# dskrdy.net
KiCad netlist of a schematic drawn in EAGLE
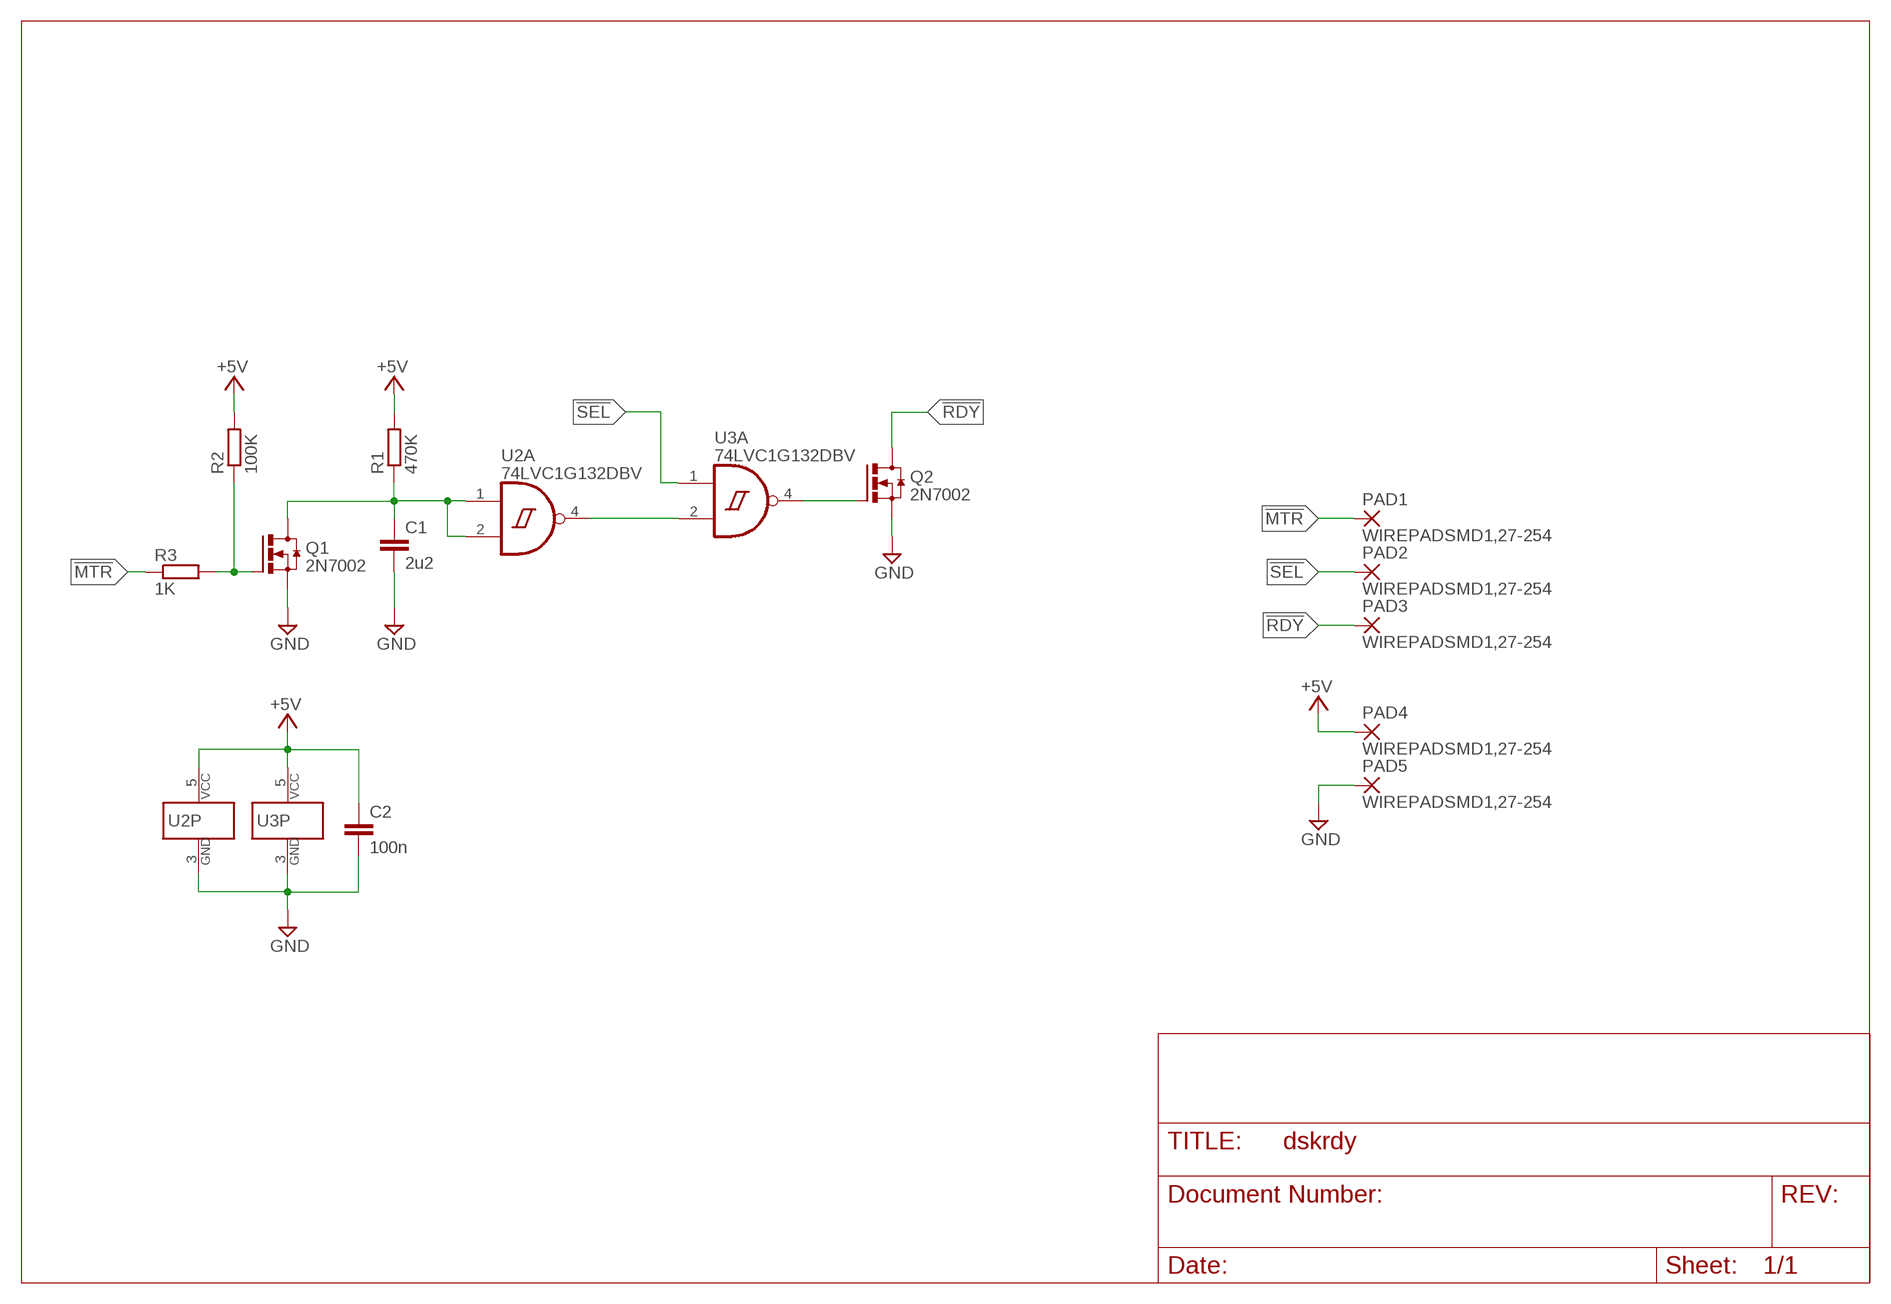
[diagram p0: schematic, sheet 1]

(export (version "E")
  (design (tool "Eeschema 10.0.6"))
  (components
    (comp (ref "C1")
      (value "2u2")
      (footprint "eagle-import:C0805")
      (libsource (lib "eagle-import") (part "C-EUC0805"))
    )
    (comp (ref "C2")
      (value "100n")
      (footprint "eagle-import:C0805")
      (libsource (lib "eagle-import") (part "C-EUC0805"))
    )
    (comp (ref "PAD1")
      (value "WIREPADSMD1,27-254")
      (footprint "eagle-import:SMD1,27-2,54")
      (libsource (lib "eagle-import") (part "WIREPADSMD1,27-254"))
    )
    (comp (ref "PAD2")
      (value "WIREPADSMD1,27-254")
      (footprint "eagle-import:SMD1,27-2,54")
      (libsource (lib "eagle-import") (part "WIREPADSMD1,27-254"))
    )
    (comp (ref "PAD3")
      (value "WIREPADSMD1,27-254")
      (footprint "eagle-import:SMD1,27-2,54")
      (libsource (lib "eagle-import") (part "WIREPADSMD1,27-254"))
    )
    (comp (ref "PAD4")
      (value "WIREPADSMD1,27-254")
      (footprint "eagle-import:SMD1,27-2,54")
      (libsource (lib "eagle-import") (part "WIREPADSMD1,27-254"))
    )
    (comp (ref "PAD5")
      (value "WIREPADSMD1,27-254")
      (footprint "eagle-import:SMD1,27-2,54")
      (libsource (lib "eagle-import") (part "WIREPADSMD1,27-254"))
    )
    (comp (ref "Q1")
      (value "2N7002")
      (footprint "eagle-import:SOT23")
      (libsource (lib "eagle-import") (part "-NMOS_?SOT23"))
    )
    (comp (ref "Q2")
      (value "2N7002")
      (footprint "eagle-import:SOT23")
      (libsource (lib "eagle-import") (part "-NMOS_?SOT23"))
    )
    (comp (ref "R1")
      (value "470K")
      (footprint "eagle-import:R0805")
      (libsource (lib "eagle-import") (part "R-EU_R0805"))
    )
    (comp (ref "R2")
      (value "100K")
      (footprint "eagle-import:R0805")
      (libsource (lib "eagle-import") (part "R-EU_R0805"))
    )
    (comp (ref "R3")
      (value "1K")
      (footprint "eagle-import:R0805")
      (libsource (lib "eagle-import") (part "R-EU_R0805"))
    )
    (comp (ref "U2")
      (value "74LVC1G132DBV")
      (footprint "eagle-import:SOT23-5")
      (libsource (lib "eagle-import") (part "741G132DBVLVC"))
    )
    (comp (ref "U3")
      (value "74LVC1G132DBV")
      (footprint "eagle-import:SOT23-5")
      (libsource (lib "eagle-import") (part "741G132DBVLVC"))
    )
  )
  (nets
    (net (code "1") (name "+5V") (class "Default")
      (node (ref "C2") (pin "1") (pinfunction "1_1") (pintype "passive"))
      (node (ref "PAD4") (pin "1") (pinfunction "P_1") (pintype "passive"))
      (node (ref "R1") (pin "2") (pinfunction "2_2") (pintype "passive"))
      (node (ref "R2") (pin "2") (pinfunction "2_2") (pintype "passive"))
      (node (ref "U2") (pin "5") (pinfunction "VCC_5") (pintype "power_in"))
      (node (ref "U3") (pin "5") (pinfunction "VCC_5") (pintype "power_in"))
    )
    (net (code "2") (name "/~{MTR}") (class "Default")
      (node (ref "PAD1") (pin "1") (pinfunction "P_1") (pintype "passive"))
      (node (ref "R3") (pin "1") (pinfunction "1_1") (pintype "passive"))
    )
    (net (code "3") (name "/~{RDY}") (class "Default")
      (node (ref "PAD3") (pin "1") (pinfunction "P_1") (pintype "passive"))
      (node (ref "Q2") (pin "3") (pinfunction "D_3") (pintype "passive"))
    )
    (net (code "4") (name "/~{SEL}") (class "Default")
      (node (ref "PAD2") (pin "1") (pinfunction "P_1") (pintype "passive"))
      (node (ref "U3") (pin "1") (pinfunction "I0_1") (pintype "input"))
    )
    (net (code "5") (name "GND") (class "Default")
      (node (ref "C1") (pin "2") (pinfunction "2_2") (pintype "passive"))
      (node (ref "C2") (pin "2") (pinfunction "2_2") (pintype "passive"))
      (node (ref "PAD5") (pin "1") (pinfunction "P_1") (pintype "passive"))
      (node (ref "Q1") (pin "2") (pinfunction "S_2") (pintype "passive"))
      (node (ref "Q2") (pin "2") (pinfunction "S_2") (pintype "passive"))
      (node (ref "U2") (pin "3") (pinfunction "GND_3") (pintype "power_in"))
      (node (ref "U3") (pin "3") (pinfunction "GND_3") (pintype "power_in"))
    )
    (net (code "6") (name "Net-(Q1-D)") (class "Default")
      (node (ref "C1") (pin "1") (pinfunction "1_1") (pintype "passive"))
      (node (ref "Q1") (pin "3") (pinfunction "D_3") (pintype "passive"))
      (node (ref "R1") (pin "1") (pinfunction "1_1") (pintype "passive"))
      (node (ref "U2") (pin "1") (pinfunction "I0_1") (pintype "input"))
      (node (ref "U2") (pin "2") (pinfunction "I1_2") (pintype "input"))
    )
    (net (code "7") (name "Net-(Q1-G)") (class "Default")
      (node (ref "Q1") (pin "1") (pinfunction "G_1") (pintype "passive"))
      (node (ref "R2") (pin "1") (pinfunction "1_1") (pintype "passive"))
      (node (ref "R3") (pin "2") (pinfunction "2_2") (pintype "passive"))
    )
    (net (code "8") (name "Net-(Q2-G)") (class "Default")
      (node (ref "Q2") (pin "1") (pinfunction "G_1") (pintype "passive"))
      (node (ref "U3") (pin "4") (pinfunction "O_4") (pintype "output"))
    )
    (net (code "9") (name "Net-(U2A-O)") (class "Default")
      (node (ref "U2") (pin "4") (pinfunction "O_4") (pintype "output"))
      (node (ref "U3") (pin "2") (pinfunction "I1_2") (pintype "input"))
    )
  )
)
